# ardIOExp.net
KiCad netlist of a schematic drawn in EAGLE
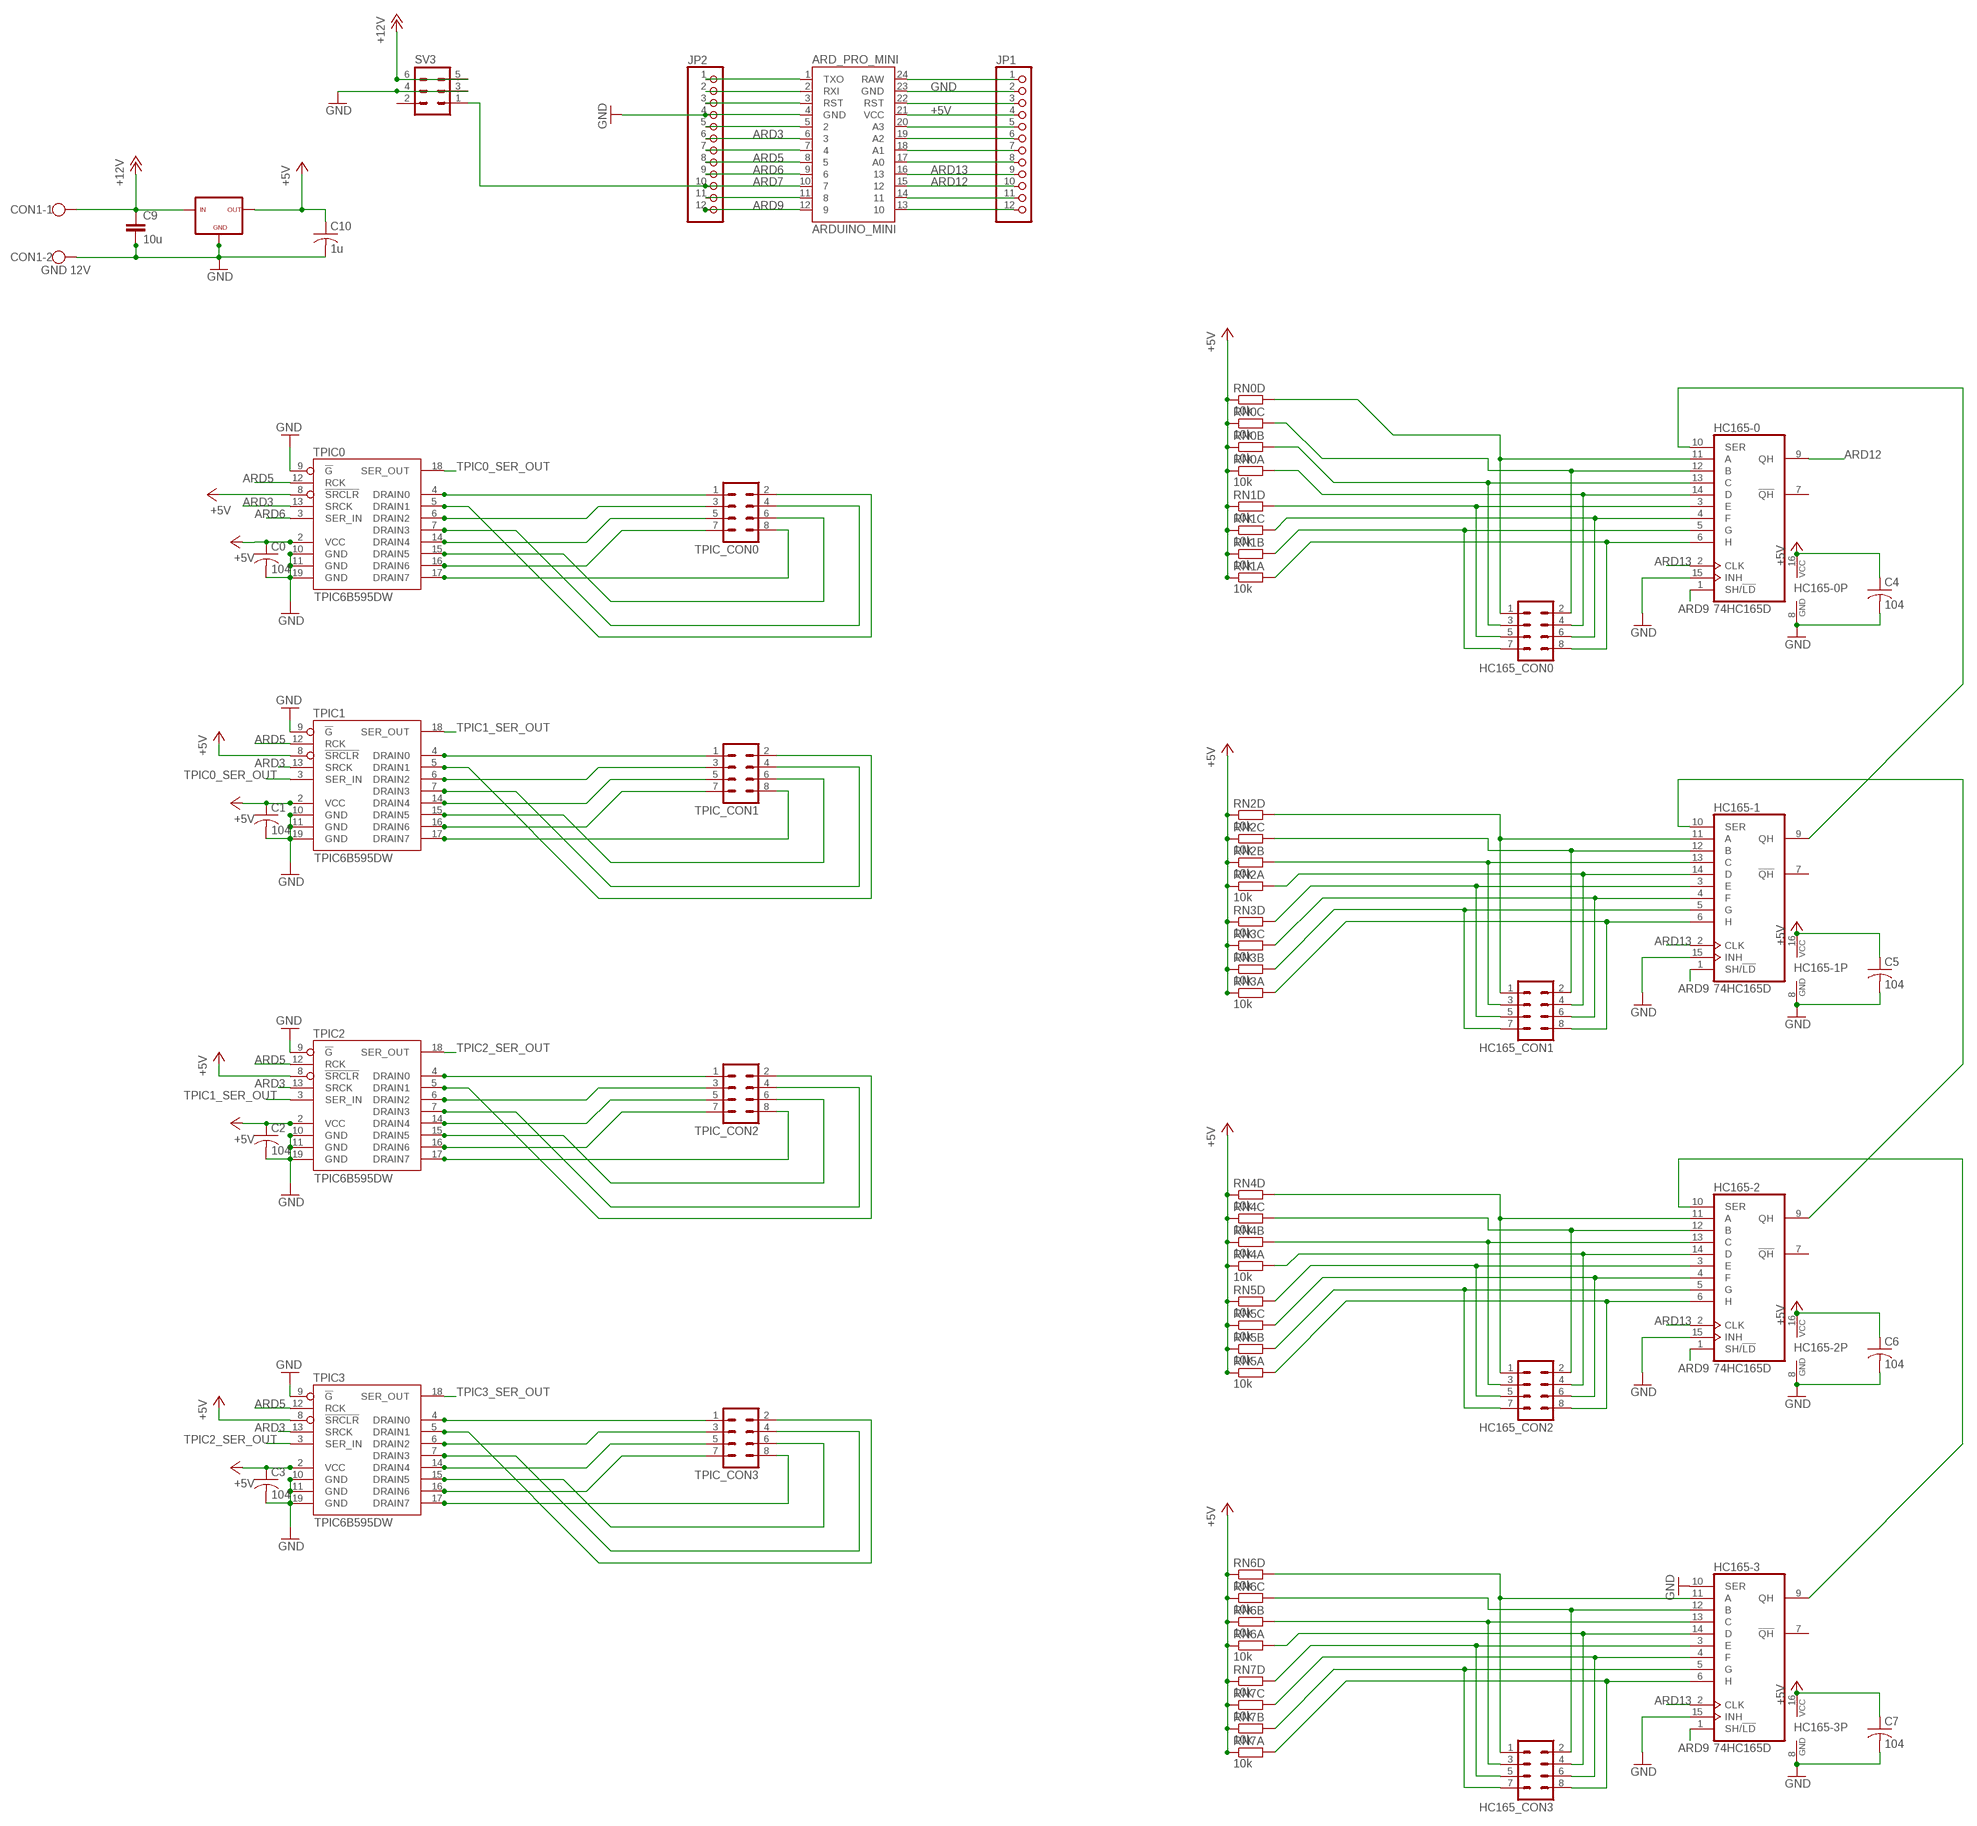
[diagram p0: schematic, sheet 1]

(export (version "E")
  (design (tool "Eeschema 10.0.6"))
  (components
    (comp (ref "ARD_PRO_MINI")
      (value "ARDUINO_MINI")
      (footprint "eagle-import:ARDUINO_MINI")
      (libsource (lib "eagle-import") (part "ARDUINO_MINI"))
    )
    (comp (ref "C0")
      (value "104")
      (footprint "eagle-import:C0603")
      (libsource (lib "eagle-import") (part "C-USC0603"))
    )
    (comp (ref "C1")
      (value "104")
      (footprint "eagle-import:C0603")
      (libsource (lib "eagle-import") (part "C-USC0603"))
    )
    (comp (ref "C2")
      (value "104")
      (footprint "eagle-import:C0603")
      (libsource (lib "eagle-import") (part "C-USC0603"))
    )
    (comp (ref "C3")
      (value "104")
      (footprint "eagle-import:C0603")
      (libsource (lib "eagle-import") (part "C-USC0603"))
    )
    (comp (ref "C4")
      (value "104")
      (footprint "eagle-import:C0603")
      (libsource (lib "eagle-import") (part "C-USC0603"))
    )
    (comp (ref "C5")
      (value "104")
      (footprint "eagle-import:C0603")
      (libsource (lib "eagle-import") (part "C-USC0603"))
    )
    (comp (ref "C6")
      (value "104")
      (footprint "eagle-import:C0603")
      (libsource (lib "eagle-import") (part "C-USC0603"))
    )
    (comp (ref "C7")
      (value "104")
      (footprint "eagle-import:C0603")
      (libsource (lib "eagle-import") (part "C-USC0603"))
    )
    (comp (ref "C9")
      (value "10u")
      (footprint "eagle-import:C050-024X044")
      (libsource (lib "eagle-import") (part "C-EU050-024X044"))
    )
    (comp (ref "C10")
      (value "1u")
      (footprint "eagle-import:C0805")
      (libsource (lib "eagle-import") (part "C-USC0805"))
    )
    (comp (ref "CON1")
      (value "GND 12V")
      (footprint "eagle-import:W237-102")
      (fields (field (name "MPN") "237-102"))
      (libsource (lib "eagle-import") (part "W237-102"))
    )
    (comp (ref "HC165-0")
      (value "74HC165D")
      (footprint "eagle-import:SO16")
      (libsource (lib "eagle-import") (part "74165DHC"))
    )
    (comp (ref "HC165-1")
      (value "74HC165D")
      (footprint "eagle-import:SO16")
      (libsource (lib "eagle-import") (part "74165DHC"))
    )
    (comp (ref "HC165-2")
      (value "74HC165D")
      (footprint "eagle-import:SO16")
      (libsource (lib "eagle-import") (part "74165DHC"))
    )
    (comp (ref "HC165-3")
      (value "74HC165D")
      (footprint "eagle-import:SO16")
      (libsource (lib "eagle-import") (part "74165DHC"))
    )
    (comp (ref "HC165_CON0")
      (value "MA04-2")
      (footprint "eagle-import:MA04-2")
      (libsource (lib "eagle-import") (part "MA04-2"))
    )
    (comp (ref "HC165_CON1")
      (value "MA04-2")
      (footprint "eagle-import:MA04-2")
      (libsource (lib "eagle-import") (part "MA04-2"))
    )
    (comp (ref "HC165_CON2")
      (value "MA04-2")
      (footprint "eagle-import:MA04-2")
      (libsource (lib "eagle-import") (part "MA04-2"))
    )
    (comp (ref "HC165_CON3")
      (value "MA04-2")
      (footprint "eagle-import:MA04-2")
      (libsource (lib "eagle-import") (part "MA04-2"))
    )
    (comp (ref "JP1")
      (value "PINHD-1X12-CB")
      (footprint "eagle-import:1X12-CB")
      (libsource (lib "eagle-import") (part "PINHD-1X12-CB"))
    )
    (comp (ref "JP2")
      (value "PINHD-1X12-CB")
      (footprint "eagle-import:1X12-CB")
      (libsource (lib "eagle-import") (part "PINHD-1X12-CB"))
    )
    (comp (ref "RN0")
      (value "10k")
      (footprint "eagle-import:RN8P-4R-CRA06S")
      (libsource (lib "eagle-import") (part "RESISTOR_ARRAY_4"))
    )
    (comp (ref "RN1")
      (value "10k")
      (footprint "eagle-import:RN8P-4R-CRA06S")
      (libsource (lib "eagle-import") (part "RESISTOR_ARRAY_4"))
    )
    (comp (ref "RN2")
      (value "10k")
      (footprint "eagle-import:RN8P-4R-CRA06S")
      (libsource (lib "eagle-import") (part "RESISTOR_ARRAY_4"))
    )
    (comp (ref "RN3")
      (value "10k")
      (footprint "eagle-import:RN8P-4R-CRA06S")
      (libsource (lib "eagle-import") (part "RESISTOR_ARRAY_4"))
    )
    (comp (ref "RN4")
      (value "10k")
      (footprint "eagle-import:RN8P-4R-CRA06S")
      (libsource (lib "eagle-import") (part "RESISTOR_ARRAY_4"))
    )
    (comp (ref "RN5")
      (value "10k")
      (footprint "eagle-import:RN8P-4R-CRA06S")
      (libsource (lib "eagle-import") (part "RESISTOR_ARRAY_4"))
    )
    (comp (ref "RN6")
      (value "10k")
      (footprint "eagle-import:RN8P-4R-CRA06S")
      (libsource (lib "eagle-import") (part "RESISTOR_ARRAY_4"))
    )
    (comp (ref "RN7")
      (value "10k")
      (footprint "eagle-import:RN8P-4R-CRA06S")
      (libsource (lib "eagle-import") (part "RESISTOR_ARRAY_4"))
    )
    (comp (ref "SV3")
      (value "MA03-2")
      (footprint "eagle-import:MA03-2")
      (libsource (lib "eagle-import") (part "MA03-2"))
    )
    (comp (ref "TPIC0")
      (value "TPIC6B595DW")
      (footprint "eagle-import:SO20W")
      (libsource (lib "eagle-import") (part "TPIC6B595DW"))
    )
    (comp (ref "TPIC1")
      (value "TPIC6B595DW")
      (footprint "eagle-import:SO20W")
      (libsource (lib "eagle-import") (part "TPIC6B595DW"))
    )
    (comp (ref "TPIC2")
      (value "TPIC6B595DW")
      (footprint "eagle-import:SO20W")
      (libsource (lib "eagle-import") (part "TPIC6B595DW"))
    )
    (comp (ref "TPIC3")
      (value "TPIC6B595DW")
      (footprint "eagle-import:SO20W")
      (libsource (lib "eagle-import") (part "TPIC6B595DW"))
    )
    (comp (ref "TPIC_CON0")
      (value "MA04-2")
      (footprint "eagle-import:MA04-2")
      (libsource (lib "eagle-import") (part "MA04-2"))
    )
    (comp (ref "TPIC_CON1")
      (value "MA04-2")
      (footprint "eagle-import:MA04-2")
      (libsource (lib "eagle-import") (part "MA04-2"))
    )
    (comp (ref "TPIC_CON2")
      (value "MA04-2")
      (footprint "eagle-import:MA04-2")
      (libsource (lib "eagle-import") (part "MA04-2"))
    )
    (comp (ref "TPIC_CON3")
      (value "MA04-2")
      (footprint "eagle-import:MA04-2")
      (libsource (lib "eagle-import") (part "MA04-2"))
    )
    (comp (ref "V_REG_5V")
      (value "L78D2TT")
      (footprint "eagle-import:D2PAK")
      (libsource (lib "eagle-import") (part "L78D2TT"))
    )
  )
  (nets
    (net (code "1") (name "+5V") (class "Default")
      (node (ref "ARD_PRO_MINI") (pin "21") (pinfunction "VCC_21") (pintype "bidirectional"))
      (node (ref "C0") (pin "1") (pinfunction "1_1") (pintype "passive"))
      (node (ref "C1") (pin "1") (pinfunction "1_1") (pintype "passive"))
      (node (ref "C10") (pin "1") (pinfunction "1_1") (pintype "passive"))
      (node (ref "C2") (pin "1") (pinfunction "1_1") (pintype "passive"))
      (node (ref "C3") (pin "1") (pinfunction "1_1") (pintype "passive"))
      (node (ref "C4") (pin "1") (pinfunction "1_1") (pintype "passive"))
      (node (ref "C5") (pin "1") (pinfunction "1_1") (pintype "passive"))
      (node (ref "C6") (pin "1") (pinfunction "1_1") (pintype "passive"))
      (node (ref "C7") (pin "1") (pinfunction "1_1") (pintype "passive"))
      (node (ref "HC165-0") (pin "16") (pinfunction "VCC_16") (pintype "power_in"))
      (node (ref "HC165-1") (pin "16") (pinfunction "VCC_16") (pintype "power_in"))
      (node (ref "HC165-2") (pin "16") (pinfunction "VCC_16") (pintype "power_in"))
      (node (ref "HC165-3") (pin "16") (pinfunction "VCC_16") (pintype "power_in"))
      (node (ref "JP1") (pin "4") (pinfunction "4_4") (pintype "passive"))
      (node (ref "RN0") (pin "1") (pinfunction "1_1") (pintype "passive"))
      (node (ref "RN0") (pin "2") (pinfunction "1_2") (pintype "passive"))
      (node (ref "RN0") (pin "3") (pinfunction "1_3") (pintype "passive"))
      (node (ref "RN0") (pin "4") (pinfunction "1_4") (pintype "passive"))
      (node (ref "RN1") (pin "1") (pinfunction "1_1") (pintype "passive"))
      (node (ref "RN1") (pin "2") (pinfunction "1_2") (pintype "passive"))
      (node (ref "RN1") (pin "3") (pinfunction "1_3") (pintype "passive"))
      (node (ref "RN1") (pin "4") (pinfunction "1_4") (pintype "passive"))
      (node (ref "RN2") (pin "1") (pinfunction "1_1") (pintype "passive"))
      (node (ref "RN2") (pin "2") (pinfunction "1_2") (pintype "passive"))
      (node (ref "RN2") (pin "3") (pinfunction "1_3") (pintype "passive"))
      (node (ref "RN2") (pin "4") (pinfunction "1_4") (pintype "passive"))
      (node (ref "RN3") (pin "1") (pinfunction "1_1") (pintype "passive"))
      (node (ref "RN3") (pin "2") (pinfunction "1_2") (pintype "passive"))
      (node (ref "RN3") (pin "3") (pinfunction "1_3") (pintype "passive"))
      (node (ref "RN3") (pin "4") (pinfunction "1_4") (pintype "passive"))
      (node (ref "RN4") (pin "1") (pinfunction "1_1") (pintype "passive"))
      (node (ref "RN4") (pin "2") (pinfunction "1_2") (pintype "passive"))
      (node (ref "RN4") (pin "3") (pinfunction "1_3") (pintype "passive"))
      (node (ref "RN4") (pin "4") (pinfunction "1_4") (pintype "passive"))
      (node (ref "RN5") (pin "1") (pinfunction "1_1") (pintype "passive"))
      (node (ref "RN5") (pin "2") (pinfunction "1_2") (pintype "passive"))
      (node (ref "RN5") (pin "3") (pinfunction "1_3") (pintype "passive"))
      (node (ref "RN5") (pin "4") (pinfunction "1_4") (pintype "passive"))
      (node (ref "RN6") (pin "1") (pinfunction "1_1") (pintype "passive"))
      (node (ref "RN6") (pin "2") (pinfunction "1_2") (pintype "passive"))
      (node (ref "RN6") (pin "3") (pinfunction "1_3") (pintype "passive"))
      (node (ref "RN6") (pin "4") (pinfunction "1_4") (pintype "passive"))
      (node (ref "RN7") (pin "1") (pinfunction "1_1") (pintype "passive"))
      (node (ref "RN7") (pin "2") (pinfunction "1_2") (pintype "passive"))
      (node (ref "RN7") (pin "3") (pinfunction "1_3") (pintype "passive"))
      (node (ref "RN7") (pin "4") (pinfunction "1_4") (pintype "passive"))
      (node (ref "TPIC0") (pin "2") (pinfunction "VCC_2") (pintype "power_in"))
      (node (ref "TPIC0") (pin "8") (pinfunction "~{SRCLR}_8") (pintype "input"))
      (node (ref "TPIC1") (pin "2") (pinfunction "VCC_2") (pintype "power_in"))
      (node (ref "TPIC1") (pin "8") (pinfunction "~{SRCLR}_8") (pintype "input"))
      (node (ref "TPIC2") (pin "2") (pinfunction "VCC_2") (pintype "power_in"))
      (node (ref "TPIC2") (pin "8") (pinfunction "~{SRCLR}_8") (pintype "input"))
      (node (ref "TPIC3") (pin "2") (pinfunction "VCC_2") (pintype "power_in"))
      (node (ref "TPIC3") (pin "8") (pinfunction "~{SRCLR}_8") (pintype "input"))
      (node (ref "V_REG_5V") (pin "3") (pinfunction "OUT_3") (pintype "passive"))
    )
    (net (code "2") (name "+12V") (class "Default")
      (node (ref "C9") (pin "1") (pinfunction "1_1") (pintype "passive"))
      (node (ref "CON1") (pin "1") (pinfunction "KL_1") (pintype "passive"))
      (node (ref "SV3") (pin "5") (pinfunction "5_5") (pintype "passive"))
      (node (ref "SV3") (pin "6") (pinfunction "6_6") (pintype "passive"))
      (node (ref "V_REG_5V") (pin "1") (pinfunction "IN_1") (pintype "input"))
    )
    (net (code "3") (name "/ARD3") (class "Default")
      (node (ref "ARD_PRO_MINI") (pin "6") (pinfunction "3_6") (pintype "bidirectional"))
      (node (ref "JP2") (pin "6") (pinfunction "6_6") (pintype "passive"))
      (node (ref "TPIC0") (pin "13") (pinfunction "SRCK_13") (pintype "input"))
      (node (ref "TPIC1") (pin "13") (pinfunction "SRCK_13") (pintype "input"))
      (node (ref "TPIC2") (pin "13") (pinfunction "SRCK_13") (pintype "input"))
      (node (ref "TPIC3") (pin "13") (pinfunction "SRCK_13") (pintype "input"))
    )
    (net (code "4") (name "/ARD5") (class "Default")
      (node (ref "ARD_PRO_MINI") (pin "8") (pinfunction "5_8") (pintype "bidirectional"))
      (node (ref "JP2") (pin "8") (pinfunction "8_8") (pintype "passive"))
      (node (ref "TPIC0") (pin "12") (pinfunction "RCK_12") (pintype "input"))
      (node (ref "TPIC1") (pin "12") (pinfunction "RCK_12") (pintype "input"))
      (node (ref "TPIC2") (pin "12") (pinfunction "RCK_12") (pintype "input"))
      (node (ref "TPIC3") (pin "12") (pinfunction "RCK_12") (pintype "input"))
    )
    (net (code "5") (name "/ARD6") (class "Default")
      (node (ref "ARD_PRO_MINI") (pin "9") (pinfunction "6_9") (pintype "bidirectional"))
      (node (ref "JP2") (pin "9") (pinfunction "9_9") (pintype "passive"))
      (node (ref "TPIC0") (pin "3") (pinfunction "SER_IN_3") (pintype "input"))
    )
    (net (code "6") (name "/ARD7") (class "Default")
      (node (ref "ARD_PRO_MINI") (pin "10") (pinfunction "7_10") (pintype "bidirectional"))
      (node (ref "JP2") (pin "10") (pinfunction "10_10") (pintype "passive"))
      (node (ref "SV3") (pin "1") (pinfunction "1_1") (pintype "passive"))
    )
    (net (code "7") (name "/ARD9") (class "Default")
      (node (ref "ARD_PRO_MINI") (pin "12") (pinfunction "9_12") (pintype "bidirectional"))
      (node (ref "HC165-0") (pin "1") (pinfunction "SH/~{LD}_1") (pintype "input"))
      (node (ref "HC165-1") (pin "1") (pinfunction "SH/~{LD}_1") (pintype "input"))
      (node (ref "HC165-2") (pin "1") (pinfunction "SH/~{LD}_1") (pintype "input"))
      (node (ref "HC165-3") (pin "1") (pinfunction "SH/~{LD}_1") (pintype "input"))
      (node (ref "JP2") (pin "12") (pinfunction "12_12") (pintype "passive"))
    )
    (net (code "8") (name "/ARD12") (class "Default")
      (node (ref "ARD_PRO_MINI") (pin "15") (pinfunction "12_15") (pintype "bidirectional"))
      (node (ref "HC165-0") (pin "9") (pinfunction "QH_9") (pintype "output"))
      (node (ref "JP1") (pin "10") (pinfunction "10_10") (pintype "passive"))
    )
    (net (code "9") (name "/ARD13") (class "Default")
      (node (ref "ARD_PRO_MINI") (pin "16") (pinfunction "13_16") (pintype "bidirectional"))
      (node (ref "HC165-0") (pin "2") (pinfunction "CLK_2") (pintype "input"))
      (node (ref "HC165-1") (pin "2") (pinfunction "CLK_2") (pintype "input"))
      (node (ref "HC165-2") (pin "2") (pinfunction "CLK_2") (pintype "input"))
      (node (ref "HC165-3") (pin "2") (pinfunction "CLK_2") (pintype "input"))
      (node (ref "JP1") (pin "9") (pinfunction "9_9") (pintype "passive"))
    )
    (net (code "10") (name "/TPIC0_SER_OUT") (class "Default")
      (node (ref "TPIC0") (pin "18") (pinfunction "SER_OUT_18") (pintype "output"))
      (node (ref "TPIC1") (pin "3") (pinfunction "SER_IN_3") (pintype "input"))
    )
    (net (code "11") (name "/TPIC1_SER_OUT") (class "Default")
      (node (ref "TPIC1") (pin "18") (pinfunction "SER_OUT_18") (pintype "output"))
      (node (ref "TPIC2") (pin "3") (pinfunction "SER_IN_3") (pintype "input"))
    )
    (net (code "12") (name "/TPIC2_SER_OUT") (class "Default")
      (node (ref "TPIC2") (pin "18") (pinfunction "SER_OUT_18") (pintype "output"))
      (node (ref "TPIC3") (pin "3") (pinfunction "SER_IN_3") (pintype "input"))
    )
    (net (code "13") (name "/TPIC3_SER_OUT") (class "Default")
      (node (ref "TPIC3") (pin "18") (pinfunction "SER_OUT_18") (pintype "output"))
    )
    (net (code "14") (name "GND") (class "Default")
      (node (ref "ARD_PRO_MINI") (pin "23") (pinfunction "GND_23") (pintype "bidirectional"))
      (node (ref "ARD_PRO_MINI") (pin "4") (pinfunction "GND_4") (pintype "bidirectional"))
      (node (ref "C0") (pin "2") (pinfunction "2_2") (pintype "passive"))
      (node (ref "C1") (pin "2") (pinfunction "2_2") (pintype "passive"))
      (node (ref "C10") (pin "2") (pinfunction "2_2") (pintype "passive"))
      (node (ref "C2") (pin "2") (pinfunction "2_2") (pintype "passive"))
      (node (ref "C3") (pin "2") (pinfunction "2_2") (pintype "passive"))
      (node (ref "C4") (pin "2") (pinfunction "2_2") (pintype "passive"))
      (node (ref "C5") (pin "2") (pinfunction "2_2") (pintype "passive"))
      (node (ref "C6") (pin "2") (pinfunction "2_2") (pintype "passive"))
      (node (ref "C7") (pin "2") (pinfunction "2_2") (pintype "passive"))
      (node (ref "C9") (pin "2") (pinfunction "2_2") (pintype "passive"))
      (node (ref "CON1") (pin "2") (pinfunction "KL_2") (pintype "passive"))
      (node (ref "HC165-0") (pin "15") (pinfunction "INH_15") (pintype "input"))
      (node (ref "HC165-0") (pin "8") (pinfunction "GND_8") (pintype "power_in"))
      (node (ref "HC165-1") (pin "15") (pinfunction "INH_15") (pintype "input"))
      (node (ref "HC165-1") (pin "8") (pinfunction "GND_8") (pintype "power_in"))
      (node (ref "HC165-2") (pin "15") (pinfunction "INH_15") (pintype "input"))
      (node (ref "HC165-2") (pin "8") (pinfunction "GND_8") (pintype "power_in"))
      (node (ref "HC165-3") (pin "10") (pinfunction "SER_10") (pintype "input"))
      (node (ref "HC165-3") (pin "15") (pinfunction "INH_15") (pintype "input"))
      (node (ref "HC165-3") (pin "8") (pinfunction "GND_8") (pintype "power_in"))
      (node (ref "JP1") (pin "2") (pinfunction "2_2") (pintype "passive"))
      (node (ref "JP2") (pin "4") (pinfunction "4_4") (pintype "passive"))
      (node (ref "SV3") (pin "3") (pinfunction "3_3") (pintype "passive"))
      (node (ref "SV3") (pin "4") (pinfunction "4_4") (pintype "passive"))
      (node (ref "TPIC0") (pin "10") (pinfunction "GND_10") (pintype "power_in"))
      (node (ref "TPIC0") (pin "11") (pinfunction "GND_11") (pintype "power_in"))
      (node (ref "TPIC0") (pin "19") (pinfunction "GND_19") (pintype "power_in"))
      (node (ref "TPIC0") (pin "9") (pinfunction "~{G}_9") (pintype "input"))
      (node (ref "TPIC1") (pin "10") (pinfunction "GND_10") (pintype "power_in"))
      (node (ref "TPIC1") (pin "11") (pinfunction "GND_11") (pintype "power_in"))
      (node (ref "TPIC1") (pin "19") (pinfunction "GND_19") (pintype "power_in"))
      (node (ref "TPIC1") (pin "9") (pinfunction "~{G}_9") (pintype "input"))
      (node (ref "TPIC2") (pin "10") (pinfunction "GND_10") (pintype "power_in"))
      (node (ref "TPIC2") (pin "11") (pinfunction "GND_11") (pintype "power_in"))
      (node (ref "TPIC2") (pin "19") (pinfunction "GND_19") (pintype "power_in"))
      (node (ref "TPIC2") (pin "9") (pinfunction "~{G}_9") (pintype "input"))
      (node (ref "TPIC3") (pin "10") (pinfunction "GND_10") (pintype "power_in"))
      (node (ref "TPIC3") (pin "11") (pinfunction "GND_11") (pintype "power_in"))
      (node (ref "TPIC3") (pin "19") (pinfunction "GND_19") (pintype "power_in"))
      (node (ref "TPIC3") (pin "9") (pinfunction "~{G}_9") (pintype "input"))
      (node (ref "V_REG_5V") (pin "2") (pinfunction "GND_2") (pintype "input"))
    )
    (net (code "15") (name "Net-(ARD_PRO_MINI-2)") (class "Default")
      (node (ref "ARD_PRO_MINI") (pin "5") (pinfunction "2_5") (pintype "bidirectional"))
      (node (ref "JP2") (pin "5") (pinfunction "5_5") (pintype "passive"))
    )
    (net (code "16") (name "Net-(ARD_PRO_MINI-4)") (class "Default")
      (node (ref "ARD_PRO_MINI") (pin "7") (pinfunction "4_7") (pintype "bidirectional"))
      (node (ref "JP2") (pin "7") (pinfunction "7_7") (pintype "passive"))
    )
    (net (code "17") (name "Net-(ARD_PRO_MINI-8)") (class "Default")
      (node (ref "ARD_PRO_MINI") (pin "11") (pinfunction "8_11") (pintype "bidirectional"))
      (node (ref "JP2") (pin "11") (pinfunction "11_11") (pintype "passive"))
    )
    (net (code "18") (name "Net-(ARD_PRO_MINI-10)") (class "Default")
      (node (ref "ARD_PRO_MINI") (pin "13") (pinfunction "10_13") (pintype "bidirectional"))
      (node (ref "JP1") (pin "12") (pinfunction "12_12") (pintype "passive"))
    )
    (net (code "19") (name "Net-(ARD_PRO_MINI-11)") (class "Default")
      (node (ref "ARD_PRO_MINI") (pin "14") (pinfunction "11_14") (pintype "bidirectional"))
      (node (ref "JP1") (pin "11") (pinfunction "11_11") (pintype "passive"))
    )
    (net (code "20") (name "Net-(ARD_PRO_MINI-A0)") (class "Default")
      (node (ref "ARD_PRO_MINI") (pin "17") (pinfunction "A0_17") (pintype "bidirectional"))
      (node (ref "JP1") (pin "8") (pinfunction "8_8") (pintype "passive"))
    )
    (net (code "21") (name "Net-(ARD_PRO_MINI-A1)") (class "Default")
      (node (ref "ARD_PRO_MINI") (pin "18") (pinfunction "A1_18") (pintype "bidirectional"))
      (node (ref "JP1") (pin "7") (pinfunction "7_7") (pintype "passive"))
    )
    (net (code "22") (name "Net-(ARD_PRO_MINI-A2)") (class "Default")
      (node (ref "ARD_PRO_MINI") (pin "19") (pinfunction "A2_19") (pintype "bidirectional"))
      (node (ref "JP1") (pin "6") (pinfunction "6_6") (pintype "passive"))
    )
    (net (code "23") (name "Net-(ARD_PRO_MINI-A3)") (class "Default")
      (node (ref "ARD_PRO_MINI") (pin "20") (pinfunction "A3_20") (pintype "bidirectional"))
      (node (ref "JP1") (pin "5") (pinfunction "5_5") (pintype "passive"))
    )
    (net (code "24") (name "Net-(ARD_PRO_MINI-RAW)") (class "Default")
      (node (ref "ARD_PRO_MINI") (pin "24") (pinfunction "RAW_24") (pintype "bidirectional"))
      (node (ref "JP1") (pin "1") (pinfunction "1_1") (pintype "passive"))
    )
    (net (code "25") (name "Net-(ARD_PRO_MINI-RST-Pad3)") (class "Default")
      (node (ref "ARD_PRO_MINI") (pin "3") (pinfunction "RST_3") (pintype "bidirectional"))
      (node (ref "JP2") (pin "3") (pinfunction "3_3") (pintype "passive"))
    )
    (net (code "26") (name "Net-(ARD_PRO_MINI-RST-Pad22)") (class "Default")
      (node (ref "ARD_PRO_MINI") (pin "22") (pinfunction "RST_22") (pintype "bidirectional"))
      (node (ref "JP1") (pin "3") (pinfunction "3_3") (pintype "passive"))
    )
    (net (code "27") (name "Net-(ARD_PRO_MINI-RXI)") (class "Default")
      (node (ref "ARD_PRO_MINI") (pin "2") (pinfunction "RXI_2") (pintype "bidirectional"))
      (node (ref "JP2") (pin "2") (pinfunction "2_2") (pintype "passive"))
    )
    (net (code "28") (name "Net-(ARD_PRO_MINI-TXO)") (class "Default")
      (node (ref "ARD_PRO_MINI") (pin "1") (pinfunction "TXO_1") (pintype "bidirectional"))
      (node (ref "JP2") (pin "1") (pinfunction "1_1") (pintype "passive"))
    )
    (net (code "29") (name "Net-(HC165-0A-A)") (class "Default")
      (node (ref "HC165-0") (pin "11") (pinfunction "A_11") (pintype "input"))
      (node (ref "HC165_CON0") (pin "1") (pinfunction "1_1") (pintype "passive"))
      (node (ref "RN0") (pin "5") (pinfunction "2_5") (pintype "passive"))
    )
    (net (code "30") (name "Net-(HC165-0A-B)") (class "Default")
      (node (ref "HC165-0") (pin "12") (pinfunction "B_12") (pintype "input"))
      (node (ref "HC165_CON0") (pin "2") (pinfunction "2_2") (pintype "passive"))
      (node (ref "RN0") (pin "6") (pinfunction "2_6") (pintype "passive"))
    )
    (net (code "31") (name "Net-(HC165-0A-C)") (class "Default")
      (node (ref "HC165-0") (pin "13") (pinfunction "C_13") (pintype "input"))
      (node (ref "HC165_CON0") (pin "3") (pinfunction "3_3") (pintype "passive"))
      (node (ref "RN0") (pin "7") (pinfunction "2_7") (pintype "passive"))
    )
    (net (code "32") (name "Net-(HC165-0A-D)") (class "Default")
      (node (ref "HC165-0") (pin "14") (pinfunction "D_14") (pintype "input"))
      (node (ref "HC165_CON0") (pin "4") (pinfunction "4_4") (pintype "passive"))
      (node (ref "RN0") (pin "8") (pinfunction "2_8") (pintype "passive"))
    )
    (net (code "33") (name "Net-(HC165-0A-E)") (class "Default")
      (node (ref "HC165-0") (pin "3") (pinfunction "E_3") (pintype "input"))
      (node (ref "HC165_CON0") (pin "5") (pinfunction "5_5") (pintype "passive"))
      (node (ref "RN1") (pin "5") (pinfunction "2_5") (pintype "passive"))
    )
    (net (code "34") (name "Net-(HC165-0A-F)") (class "Default")
      (node (ref "HC165-0") (pin "4") (pinfunction "F_4") (pintype "input"))
      (node (ref "HC165_CON0") (pin "6") (pinfunction "6_6") (pintype "passive"))
      (node (ref "RN1") (pin "6") (pinfunction "2_6") (pintype "passive"))
    )
    (net (code "35") (name "Net-(HC165-0A-G)") (class "Default")
      (node (ref "HC165-0") (pin "5") (pinfunction "G_5") (pintype "input"))
      (node (ref "HC165_CON0") (pin "7") (pinfunction "7_7") (pintype "passive"))
      (node (ref "RN1") (pin "7") (pinfunction "2_7") (pintype "passive"))
    )
    (net (code "36") (name "Net-(HC165-0A-H)") (class "Default")
      (node (ref "HC165-0") (pin "6") (pinfunction "H_6") (pintype "input"))
      (node (ref "HC165_CON0") (pin "8") (pinfunction "8_8") (pintype "passive"))
      (node (ref "RN1") (pin "8") (pinfunction "2_8") (pintype "passive"))
    )
    (net (code "37") (name "Net-(HC165-0A-SER)") (class "Default")
      (node (ref "HC165-0") (pin "10") (pinfunction "SER_10") (pintype "input"))
      (node (ref "HC165-1") (pin "9") (pinfunction "QH_9") (pintype "output"))
    )
    (net (code "38") (name "Net-(HC165-1A-A)") (class "Default")
      (node (ref "HC165-1") (pin "11") (pinfunction "A_11") (pintype "input"))
      (node (ref "HC165_CON1") (pin "1") (pinfunction "1_1") (pintype "passive"))
      (node (ref "RN2") (pin "5") (pinfunction "2_5") (pintype "passive"))
    )
    (net (code "39") (name "Net-(HC165-1A-B)") (class "Default")
      (node (ref "HC165-1") (pin "12") (pinfunction "B_12") (pintype "input"))
      (node (ref "HC165_CON1") (pin "2") (pinfunction "2_2") (pintype "passive"))
      (node (ref "RN2") (pin "6") (pinfunction "2_6") (pintype "passive"))
    )
    (net (code "40") (name "Net-(HC165-1A-C)") (class "Default")
      (node (ref "HC165-1") (pin "13") (pinfunction "C_13") (pintype "input"))
      (node (ref "HC165_CON1") (pin "3") (pinfunction "3_3") (pintype "passive"))
      (node (ref "RN2") (pin "7") (pinfunction "2_7") (pintype "passive"))
    )
    (net (code "41") (name "Net-(HC165-1A-D)") (class "Default")
      (node (ref "HC165-1") (pin "14") (pinfunction "D_14") (pintype "input"))
      (node (ref "HC165_CON1") (pin "4") (pinfunction "4_4") (pintype "passive"))
      (node (ref "RN2") (pin "8") (pinfunction "2_8") (pintype "passive"))
    )
    (net (code "42") (name "Net-(HC165-1A-E)") (class "Default")
      (node (ref "HC165-1") (pin "3") (pinfunction "E_3") (pintype "input"))
      (node (ref "HC165_CON1") (pin "5") (pinfunction "5_5") (pintype "passive"))
      (node (ref "RN3") (pin "5") (pinfunction "2_5") (pintype "passive"))
    )
    (net (code "43") (name "Net-(HC165-1A-F)") (class "Default")
      (node (ref "HC165-1") (pin "4") (pinfunction "F_4") (pintype "input"))
      (node (ref "HC165_CON1") (pin "6") (pinfunction "6_6") (pintype "passive"))
      (node (ref "RN3") (pin "6") (pinfunction "2_6") (pintype "passive"))
    )
    (net (code "44") (name "Net-(HC165-1A-G)") (class "Default")
      (node (ref "HC165-1") (pin "5") (pinfunction "G_5") (pintype "input"))
      (node (ref "HC165_CON1") (pin "7") (pinfunction "7_7") (pintype "passive"))
      (node (ref "RN3") (pin "7") (pinfunction "2_7") (pintype "passive"))
    )
    (net (code "45") (name "Net-(HC165-1A-H)") (class "Default")
      (node (ref "HC165-1") (pin "6") (pinfunction "H_6") (pintype "input"))
      (node (ref "HC165_CON1") (pin "8") (pinfunction "8_8") (pintype "passive"))
      (node (ref "RN3") (pin "8") (pinfunction "2_8") (pintype "passive"))
    )
    (net (code "46") (name "Net-(HC165-1A-SER)") (class "Default")
      (node (ref "HC165-1") (pin "10") (pinfunction "SER_10") (pintype "input"))
      (node (ref "HC165-2") (pin "9") (pinfunction "QH_9") (pintype "output"))
    )
    (net (code "47") (name "Net-(HC165-2A-A)") (class "Default")
      (node (ref "HC165-2") (pin "11") (pinfunction "A_11") (pintype "input"))
      (node (ref "HC165_CON2") (pin "1") (pinfunction "1_1") (pintype "passive"))
      (node (ref "RN4") (pin "5") (pinfunction "2_5") (pintype "passive"))
    )
    (net (code "48") (name "Net-(HC165-2A-B)") (class "Default")
      (node (ref "HC165-2") (pin "12") (pinfunction "B_12") (pintype "input"))
      (node (ref "HC165_CON2") (pin "2") (pinfunction "2_2") (pintype "passive"))
      (node (ref "RN4") (pin "6") (pinfunction "2_6") (pintype "passive"))
    )
    (net (code "49") (name "Net-(HC165-2A-C)") (class "Default")
      (node (ref "HC165-2") (pin "13") (pinfunction "C_13") (pintype "input"))
      (node (ref "HC165_CON2") (pin "3") (pinfunction "3_3") (pintype "passive"))
      (node (ref "RN4") (pin "7") (pinfunction "2_7") (pintype "passive"))
    )
    (net (code "50") (name "Net-(HC165-2A-D)") (class "Default")
      (node (ref "HC165-2") (pin "14") (pinfunction "D_14") (pintype "input"))
      (node (ref "HC165_CON2") (pin "4") (pinfunction "4_4") (pintype "passive"))
      (node (ref "RN4") (pin "8") (pinfunction "2_8") (pintype "passive"))
    )
    (net (code "51") (name "Net-(HC165-2A-E)") (class "Default")
      (node (ref "HC165-2") (pin "3") (pinfunction "E_3") (pintype "input"))
      (node (ref "HC165_CON2") (pin "5") (pinfunction "5_5") (pintype "passive"))
      (node (ref "RN5") (pin "5") (pinfunction "2_5") (pintype "passive"))
    )
    (net (code "52") (name "Net-(HC165-2A-F)") (class "Default")
      (node (ref "HC165-2") (pin "4") (pinfunction "F_4") (pintype "input"))
      (node (ref "HC165_CON2") (pin "6") (pinfunction "6_6") (pintype "passive"))
      (node (ref "RN5") (pin "6") (pinfunction "2_6") (pintype "passive"))
    )
    (net (code "53") (name "Net-(HC165-2A-G)") (class "Default")
      (node (ref "HC165-2") (pin "5") (pinfunction "G_5") (pintype "input"))
      (node (ref "HC165_CON2") (pin "7") (pinfunction "7_7") (pintype "passive"))
      (node (ref "RN5") (pin "7") (pinfunction "2_7") (pintype "passive"))
    )
    (net (code "54") (name "Net-(HC165-2A-H)") (class "Default")
      (node (ref "HC165-2") (pin "6") (pinfunction "H_6") (pintype "input"))
      (node (ref "HC165_CON2") (pin "8") (pinfunction "8_8") (pintype "passive"))
      (node (ref "RN5") (pin "8") (pinfunction "2_8") (pintype "passive"))
    )
    (net (code "55") (name "Net-(HC165-2A-SER)") (class "Default")
      (node (ref "HC165-2") (pin "10") (pinfunction "SER_10") (pintype "input"))
      (node (ref "HC165-3") (pin "9") (pinfunction "QH_9") (pintype "output"))
    )
    (net (code "56") (name "Net-(HC165-3A-A)") (class "Default")
      (node (ref "HC165-3") (pin "11") (pinfunction "A_11") (pintype "input"))
      (node (ref "HC165_CON3") (pin "1") (pinfunction "1_1") (pintype "passive"))
      (node (ref "RN6") (pin "5") (pinfunction "2_5") (pintype "passive"))
    )
    (net (code "57") (name "Net-(HC165-3A-B)") (class "Default")
      (node (ref "HC165-3") (pin "12") (pinfunction "B_12") (pintype "input"))
      (node (ref "HC165_CON3") (pin "2") (pinfunction "2_2") (pintype "passive"))
      (node (ref "RN6") (pin "6") (pinfunction "2_6") (pintype "passive"))
    )
    (net (code "58") (name "Net-(HC165-3A-C)") (class "Default")
      (node (ref "HC165-3") (pin "13") (pinfunction "C_13") (pintype "input"))
      (node (ref "HC165_CON3") (pin "3") (pinfunction "3_3") (pintype "passive"))
      (node (ref "RN6") (pin "7") (pinfunction "2_7") (pintype "passive"))
    )
    (net (code "59") (name "Net-(HC165-3A-D)") (class "Default")
      (node (ref "HC165-3") (pin "14") (pinfunction "D_14") (pintype "input"))
      (node (ref "HC165_CON3") (pin "4") (pinfunction "4_4") (pintype "passive"))
      (node (ref "RN6") (pin "8") (pinfunction "2_8") (pintype "passive"))
    )
    (net (code "60") (name "Net-(HC165-3A-E)") (class "Default")
      (node (ref "HC165-3") (pin "3") (pinfunction "E_3") (pintype "input"))
      (node (ref "HC165_CON3") (pin "5") (pinfunction "5_5") (pintype "passive"))
      (node (ref "RN7") (pin "5") (pinfunction "2_5") (pintype "passive"))
    )
    (net (code "61") (name "Net-(HC165-3A-F)") (class "Default")
      (node (ref "HC165-3") (pin "4") (pinfunction "F_4") (pintype "input"))
      (node (ref "HC165_CON3") (pin "6") (pinfunction "6_6") (pintype "passive"))
      (node (ref "RN7") (pin "6") (pinfunction "2_6") (pintype "passive"))
    )
    (net (code "62") (name "Net-(HC165-3A-G)") (class "Default")
      (node (ref "HC165-3") (pin "5") (pinfunction "G_5") (pintype "input"))
      (node (ref "HC165_CON3") (pin "7") (pinfunction "7_7") (pintype "passive"))
      (node (ref "RN7") (pin "7") (pinfunction "2_7") (pintype "passive"))
    )
    (net (code "63") (name "Net-(HC165-3A-H)") (class "Default")
      (node (ref "HC165-3") (pin "6") (pinfunction "H_6") (pintype "input"))
      (node (ref "HC165_CON3") (pin "8") (pinfunction "8_8") (pintype "passive"))
      (node (ref "RN7") (pin "8") (pinfunction "2_8") (pintype "passive"))
    )
    (net (code "64") (name "Net-(TPIC0-DRAIN0)") (class "Default")
      (node (ref "TPIC0") (pin "4") (pinfunction "DRAIN0_4") (pintype "open_collector"))
      (node (ref "TPIC_CON0") (pin "1") (pinfunction "1_1") (pintype "passive"))
    )
    (net (code "65") (name "Net-(TPIC0-DRAIN1)") (class "Default")
      (node (ref "TPIC0") (pin "5") (pinfunction "DRAIN1_5") (pintype "open_collector"))
      (node (ref "TPIC_CON0") (pin "2") (pinfunction "2_2") (pintype "passive"))
    )
    (net (code "66") (name "Net-(TPIC0-DRAIN2)") (class "Default")
      (node (ref "TPIC0") (pin "6") (pinfunction "DRAIN2_6") (pintype "open_collector"))
      (node (ref "TPIC_CON0") (pin "3") (pinfunction "3_3") (pintype "passive"))
    )
    (net (code "67") (name "Net-(TPIC0-DRAIN3)") (class "Default")
      (node (ref "TPIC0") (pin "7") (pinfunction "DRAIN3_7") (pintype "open_collector"))
      (node (ref "TPIC_CON0") (pin "4") (pinfunction "4_4") (pintype "passive"))
    )
    (net (code "68") (name "Net-(TPIC0-DRAIN4)") (class "Default")
      (node (ref "TPIC0") (pin "14") (pinfunction "DRAIN4_14") (pintype "open_collector"))
      (node (ref "TPIC_CON0") (pin "5") (pinfunction "5_5") (pintype "passive"))
    )
    (net (code "69") (name "Net-(TPIC0-DRAIN5)") (class "Default")
      (node (ref "TPIC0") (pin "15") (pinfunction "DRAIN5_15") (pintype "open_collector"))
      (node (ref "TPIC_CON0") (pin "6") (pinfunction "6_6") (pintype "passive"))
    )
    (net (code "70") (name "Net-(TPIC0-DRAIN6)") (class "Default")
      (node (ref "TPIC0") (pin "16") (pinfunction "DRAIN6_16") (pintype "open_collector"))
      (node (ref "TPIC_CON0") (pin "7") (pinfunction "7_7") (pintype "passive"))
    )
    (net (code "71") (name "Net-(TPIC0-DRAIN7)") (class "Default")
      (node (ref "TPIC0") (pin "17") (pinfunction "DRAIN7_17") (pintype "open_collector"))
      (node (ref "TPIC_CON0") (pin "8") (pinfunction "8_8") (pintype "passive"))
    )
    (net (code "72") (name "Net-(TPIC1-DRAIN0)") (class "Default")
      (node (ref "TPIC1") (pin "4") (pinfunction "DRAIN0_4") (pintype "open_collector"))
      (node (ref "TPIC_CON1") (pin "1") (pinfunction "1_1") (pintype "passive"))
    )
    (net (code "73") (name "Net-(TPIC1-DRAIN1)") (class "Default")
      (node (ref "TPIC1") (pin "5") (pinfunction "DRAIN1_5") (pintype "open_collector"))
      (node (ref "TPIC_CON1") (pin "2") (pinfunction "2_2") (pintype "passive"))
    )
    (net (code "74") (name "Net-(TPIC1-DRAIN2)") (class "Default")
      (node (ref "TPIC1") (pin "6") (pinfunction "DRAIN2_6") (pintype "open_collector"))
      (node (ref "TPIC_CON1") (pin "3") (pinfunction "3_3") (pintype "passive"))
    )
    (net (code "75") (name "Net-(TPIC1-DRAIN3)") (class "Default")
      (node (ref "TPIC1") (pin "7") (pinfunction "DRAIN3_7") (pintype "open_collector"))
      (node (ref "TPIC_CON1") (pin "4") (pinfunction "4_4") (pintype "passive"))
    )
    (net (code "76") (name "Net-(TPIC1-DRAIN4)") (class "Default")
      (node (ref "TPIC1") (pin "14") (pinfunction "DRAIN4_14") (pintype "open_collector"))
      (node (ref "TPIC_CON1") (pin "5") (pinfunction "5_5") (pintype "passive"))
    )
    (net (code "77") (name "Net-(TPIC1-DRAIN5)") (class "Default")
      (node (ref "TPIC1") (pin "15") (pinfunction "DRAIN5_15") (pintype "open_collector"))
      (node (ref "TPIC_CON1") (pin "6") (pinfunction "6_6") (pintype "passive"))
    )
    (net (code "78") (name "Net-(TPIC1-DRAIN6)") (class "Default")
      (node (ref "TPIC1") (pin "16") (pinfunction "DRAIN6_16") (pintype "open_collector"))
      (node (ref "TPIC_CON1") (pin "7") (pinfunction "7_7") (pintype "passive"))
    )
    (net (code "79") (name "Net-(TPIC1-DRAIN7)") (class "Default")
      (node (ref "TPIC1") (pin "17") (pinfunction "DRAIN7_17") (pintype "open_collector"))
      (node (ref "TPIC_CON1") (pin "8") (pinfunction "8_8") (pintype "passive"))
    )
    (net (code "80") (name "Net-(TPIC2-DRAIN0)") (class "Default")
      (node (ref "TPIC2") (pin "4") (pinfunction "DRAIN0_4") (pintype "open_collector"))
      (node (ref "TPIC_CON2") (pin "1") (pinfunction "1_1") (pintype "passive"))
    )
    (net (code "81") (name "Net-(TPIC2-DRAIN1)") (class "Default")
      (node (ref "TPIC2") (pin "5") (pinfunction "DRAIN1_5") (pintype "open_collector"))
      (node (ref "TPIC_CON2") (pin "2") (pinfunction "2_2") (pintype "passive"))
    )
    (net (code "82") (name "Net-(TPIC2-DRAIN2)") (class "Default")
      (node (ref "TPIC2") (pin "6") (pinfunction "DRAIN2_6") (pintype "open_collector"))
      (node (ref "TPIC_CON2") (pin "3") (pinfunction "3_3") (pintype "passive"))
    )
    (net (code "83") (name "Net-(TPIC2-DRAIN3)") (class "Default")
      (node (ref "TPIC2") (pin "7") (pinfunction "DRAIN3_7") (pintype "open_collector"))
      (node (ref "TPIC_CON2") (pin "4") (pinfunction "4_4") (pintype "passive"))
    )
    (net (code "84") (name "Net-(TPIC2-DRAIN4)") (class "Default")
      (node (ref "TPIC2") (pin "14") (pinfunction "DRAIN4_14") (pintype "open_collector"))
      (node (ref "TPIC_CON2") (pin "5") (pinfunction "5_5") (pintype "passive"))
    )
    (net (code "85") (name "Net-(TPIC2-DRAIN5)") (class "Default")
      (node (ref "TPIC2") (pin "15") (pinfunction "DRAIN5_15") (pintype "open_collector"))
      (node (ref "TPIC_CON2") (pin "6") (pinfunction "6_6") (pintype "passive"))
    )
    (net (code "86") (name "Net-(TPIC2-DRAIN6)") (class "Default")
      (node (ref "TPIC2") (pin "16") (pinfunction "DRAIN6_16") (pintype "open_collector"))
      (node (ref "TPIC_CON2") (pin "7") (pinfunction "7_7") (pintype "passive"))
    )
    (net (code "87") (name "Net-(TPIC2-DRAIN7)") (class "Default")
      (node (ref "TPIC2") (pin "17") (pinfunction "DRAIN7_17") (pintype "open_collector"))
      (node (ref "TPIC_CON2") (pin "8") (pinfunction "8_8") (pintype "passive"))
    )
    (net (code "88") (name "Net-(TPIC3-DRAIN0)") (class "Default")
      (node (ref "TPIC3") (pin "4") (pinfunction "DRAIN0_4") (pintype "open_collector"))
      (node (ref "TPIC_CON3") (pin "1") (pinfunction "1_1") (pintype "passive"))
    )
    (net (code "89") (name "Net-(TPIC3-DRAIN1)") (class "Default")
      (node (ref "TPIC3") (pin "5") (pinfunction "DRAIN1_5") (pintype "open_collector"))
      (node (ref "TPIC_CON3") (pin "2") (pinfunction "2_2") (pintype "passive"))
    )
    (net (code "90") (name "Net-(TPIC3-DRAIN2)") (class "Default")
      (node (ref "TPIC3") (pin "6") (pinfunction "DRAIN2_6") (pintype "open_collector"))
      (node (ref "TPIC_CON3") (pin "3") (pinfunction "3_3") (pintype "passive"))
    )
    (net (code "91") (name "Net-(TPIC3-DRAIN3)") (class "Default")
      (node (ref "TPIC3") (pin "7") (pinfunction "DRAIN3_7") (pintype "open_collector"))
      (node (ref "TPIC_CON3") (pin "4") (pinfunction "4_4") (pintype "passive"))
    )
    (net (code "92") (name "Net-(TPIC3-DRAIN4)") (class "Default")
      (node (ref "TPIC3") (pin "14") (pinfunction "DRAIN4_14") (pintype "open_collector"))
      (node (ref "TPIC_CON3") (pin "5") (pinfunction "5_5") (pintype "passive"))
    )
    (net (code "93") (name "Net-(TPIC3-DRAIN5)") (class "Default")
      (node (ref "TPIC3") (pin "15") (pinfunction "DRAIN5_15") (pintype "open_collector"))
      (node (ref "TPIC_CON3") (pin "6") (pinfunction "6_6") (pintype "passive"))
    )
    (net (code "94") (name "Net-(TPIC3-DRAIN6)") (class "Default")
      (node (ref "TPIC3") (pin "16") (pinfunction "DRAIN6_16") (pintype "open_collector"))
      (node (ref "TPIC_CON3") (pin "7") (pinfunction "7_7") (pintype "passive"))
    )
    (net (code "95") (name "Net-(TPIC3-DRAIN7)") (class "Default")
      (node (ref "TPIC3") (pin "17") (pinfunction "DRAIN7_17") (pintype "open_collector"))
      (node (ref "TPIC_CON3") (pin "8") (pinfunction "8_8") (pintype "passive"))
    )
    (net (code "96") (name "unconnected-(HC165-0A-~{QH}-Pad7)") (class "Default")
      (node (ref "HC165-0") (pin "7") (pinfunction "~{QH}_7") (pintype "output"))
    )
    (net (code "97") (name "unconnected-(HC165-1A-~{QH}-Pad7)") (class "Default")
      (node (ref "HC165-1") (pin "7") (pinfunction "~{QH}_7") (pintype "output"))
    )
    (net (code "98") (name "unconnected-(HC165-2A-~{QH}-Pad7)") (class "Default")
      (node (ref "HC165-2") (pin "7") (pinfunction "~{QH}_7") (pintype "output"))
    )
    (net (code "99") (name "unconnected-(HC165-3A-~{QH}-Pad7)") (class "Default")
      (node (ref "HC165-3") (pin "7") (pinfunction "~{QH}_7") (pintype "output"))
    )
    (net (code "100") (name "unconnected-(SV3-Pad2)") (class "Default")
      (node (ref "SV3") (pin "2") (pinfunction "2_2") (pintype "passive"))
    )
  )
)
